# Qwiic_MultiPort.net
KiCad netlist of a schematic drawn in EAGLE
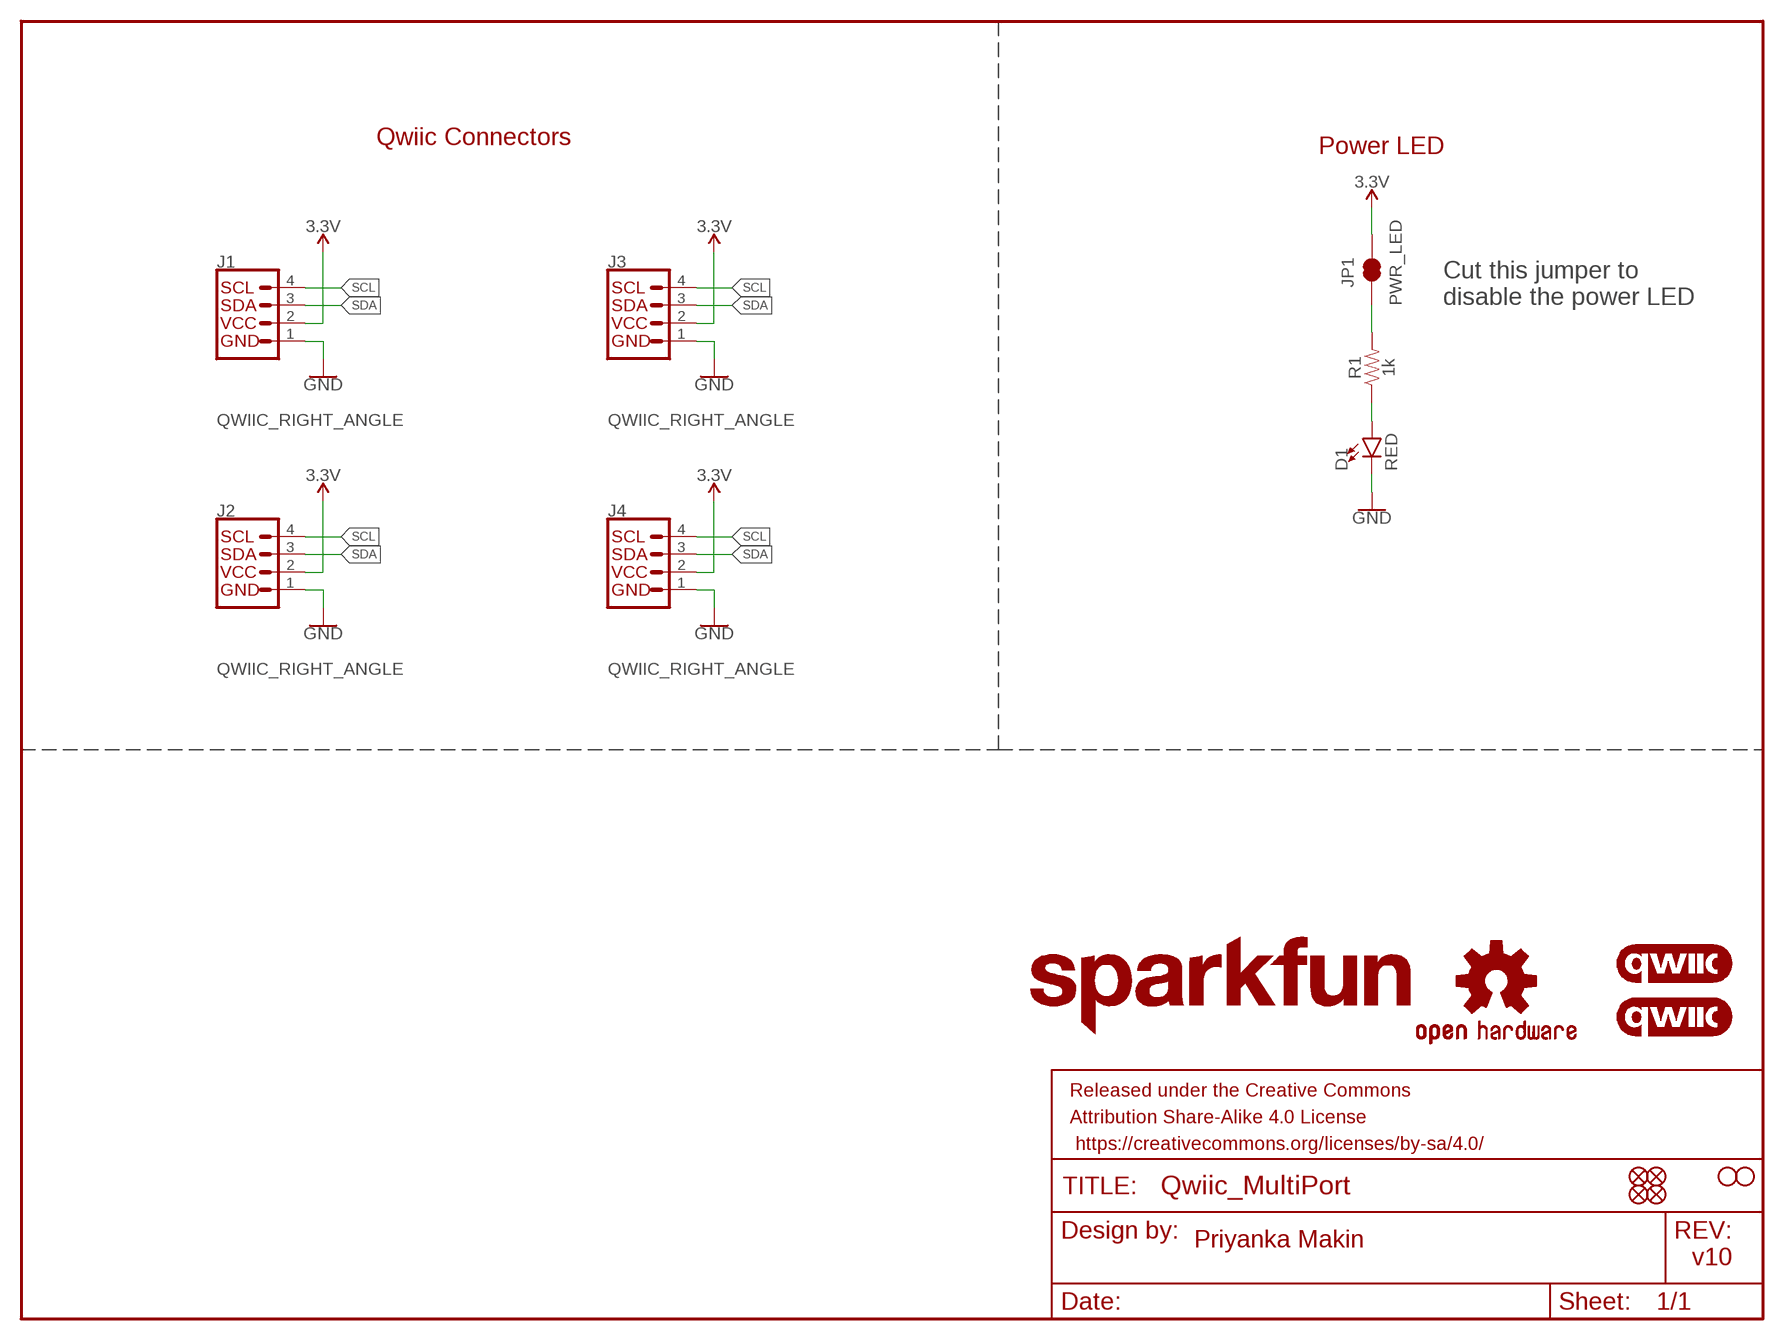
[diagram p0: schematic, sheet 1]

(export (version "E")
  (design (tool "Eeschema 10.0.6"))
  (components
    (comp (ref "D1")
      (value "RED")
      (footprint "eagle-import:LED-0603")
      (libsource (lib "eagle-import") (part "LED-RED0603"))
    )
    (comp (ref "FD1")
      (value "FIDUCIALUFIDUCIAL")
      (footprint "eagle-import:FIDUCIAL-MICRO")
      (libsource (lib "eagle-import") (part "FIDUCIALUFIDUCIAL"))
    )
    (comp (ref "FD2")
      (value "FIDUCIALUFIDUCIAL")
      (footprint "eagle-import:FIDUCIAL-MICRO")
      (libsource (lib "eagle-import") (part "FIDUCIALUFIDUCIAL"))
    )
    (comp (ref "FD3")
      (value "FIDUCIALUFIDUCIAL")
      (footprint "eagle-import:FIDUCIAL-MICRO")
      (libsource (lib "eagle-import") (part "FIDUCIALUFIDUCIAL"))
    )
    (comp (ref "FD4")
      (value "FIDUCIALUFIDUCIAL")
      (footprint "eagle-import:FIDUCIAL-MICRO")
      (libsource (lib "eagle-import") (part "FIDUCIALUFIDUCIAL"))
    )
    (comp (ref "FRAME1")
      (value "FRAME-LETTER")
      (footprint "eagle-import:CREATIVE_COMMONS")
      (libsource (lib "eagle-import") (part "FRAME-LETTER"))
    )
    (comp (ref "H1")
      (value "STAND-OFFTIGHT")
      (footprint "eagle-import:STAND-OFF-TIGHT")
      (libsource (lib "eagle-import") (part "STAND-OFFTIGHT"))
    )
    (comp (ref "H2")
      (value "STAND-OFFTIGHT")
      (footprint "eagle-import:STAND-OFF-TIGHT")
      (libsource (lib "eagle-import") (part "STAND-OFFTIGHT"))
    )
    (comp (ref "J1")
      (value "QWIIC_RIGHT_ANGLE")
      (footprint "eagle-import:JST04_1MM_RA")
      (libsource (lib "eagle-import") (part "QWIIC_CONNECTORJS-1MM"))
    )
    (comp (ref "J2")
      (value "QWIIC_RIGHT_ANGLE")
      (footprint "eagle-import:JST04_1MM_RA")
      (libsource (lib "eagle-import") (part "QWIIC_CONNECTORJS-1MM"))
    )
    (comp (ref "J3")
      (value "QWIIC_RIGHT_ANGLE")
      (footprint "eagle-import:JST04_1MM_RA")
      (libsource (lib "eagle-import") (part "QWIIC_CONNECTORJS-1MM"))
    )
    (comp (ref "J4")
      (value "QWIIC_RIGHT_ANGLE")
      (footprint "eagle-import:JST04_1MM_RA")
      (libsource (lib "eagle-import") (part "QWIIC_CONNECTORJS-1MM"))
    )
    (comp (ref "JP1")
      (value "PWR_LED")
      (footprint "eagle-import:SMT-JUMPER_2_NC_TRACE_SILK")
      (libsource (lib "eagle-import") (part "JUMPER-SMT_2_NC_TRACE_SILK"))
    )
    (comp (ref "LOGO1")
      (value "QWIIC_LOGO_5MM")
      (footprint "eagle-import:QWIIC_5MM")
      (libsource (lib "eagle-import") (part "QWIIC_LOGO_5MM"))
    )
    (comp (ref "LOGO2")
      (value "QWIIC_LOGO_5MM")
      (footprint "eagle-import:QWIIC_5MM")
      (libsource (lib "eagle-import") (part "QWIIC_LOGO_5MM"))
    )
    (comp (ref "LOGO3")
      (value "OSHW-LOGOS")
      (footprint "eagle-import:OSHW-LOGO-S")
      (libsource (lib "eagle-import") (part "OSHW-LOGOS"))
    )
    (comp (ref "LOGO4")
      (value "SFE_LOGO_NAME.2_INCH")
      (footprint "eagle-import:SFE_LOGO_NAME_.2")
      (libsource (lib "eagle-import") (part "SFE_LOGO_NAME.2_INCH"))
    )
    (comp (ref "R1")
      (value "1k")
      (footprint "eagle-import:0603")
      (libsource (lib "eagle-import") (part "1KOHM-0603-1/10W-1%"))
    )
  )
  (nets
    (net (code "1") (name "3.3V") (class "Default")
      (node (ref "J1") (pin "2") (pinfunction "2_2") (pintype "power_in"))
      (node (ref "J2") (pin "2") (pinfunction "2_2") (pintype "power_in"))
      (node (ref "J3") (pin "2") (pinfunction "2_2") (pintype "power_in"))
      (node (ref "J4") (pin "2") (pinfunction "2_2") (pintype "power_in"))
      (node (ref "JP1") (pin "2") (pinfunction "2_2") (pintype "passive"))
    )
    (net (code "2") (name "GND") (class "Default")
      (node (ref "D1") (pin "C") (pinfunction "C_C") (pintype "passive"))
      (node (ref "J1") (pin "1") (pinfunction "1_1") (pintype "power_in"))
      (node (ref "J2") (pin "1") (pinfunction "1_1") (pintype "power_in"))
      (node (ref "J3") (pin "1") (pinfunction "1_1") (pintype "power_in"))
      (node (ref "J4") (pin "1") (pinfunction "1_1") (pintype "power_in"))
    )
    (net (code "3") (name "Net-(D1-PadA)") (class "Default")
      (node (ref "D1") (pin "A") (pinfunction "A_A") (pintype "passive"))
      (node (ref "R1") (pin "1") (pinfunction "1_1") (pintype "passive"))
    )
    (net (code "4") (name "Net-(JP1-Pad1)") (class "Default")
      (node (ref "JP1") (pin "1") (pinfunction "1_1") (pintype "passive"))
      (node (ref "R1") (pin "2") (pinfunction "2_2") (pintype "passive"))
    )
    (net (code "5") (name "SCL") (class "Default")
      (node (ref "J1") (pin "4") (pinfunction "4_4") (pintype "passive"))
      (node (ref "J2") (pin "4") (pinfunction "4_4") (pintype "passive"))
      (node (ref "J3") (pin "4") (pinfunction "4_4") (pintype "passive"))
      (node (ref "J4") (pin "4") (pinfunction "4_4") (pintype "passive"))
    )
    (net (code "6") (name "SDA") (class "Default")
      (node (ref "J1") (pin "3") (pinfunction "3_3") (pintype "passive"))
      (node (ref "J2") (pin "3") (pinfunction "3_3") (pintype "passive"))
      (node (ref "J3") (pin "3") (pinfunction "3_3") (pintype "passive"))
      (node (ref "J4") (pin "3") (pinfunction "3_3") (pintype "passive"))
    )
  )
)
